# Controllerv2_s_7.net
KiCad netlist of a schematic drawn in EAGLE
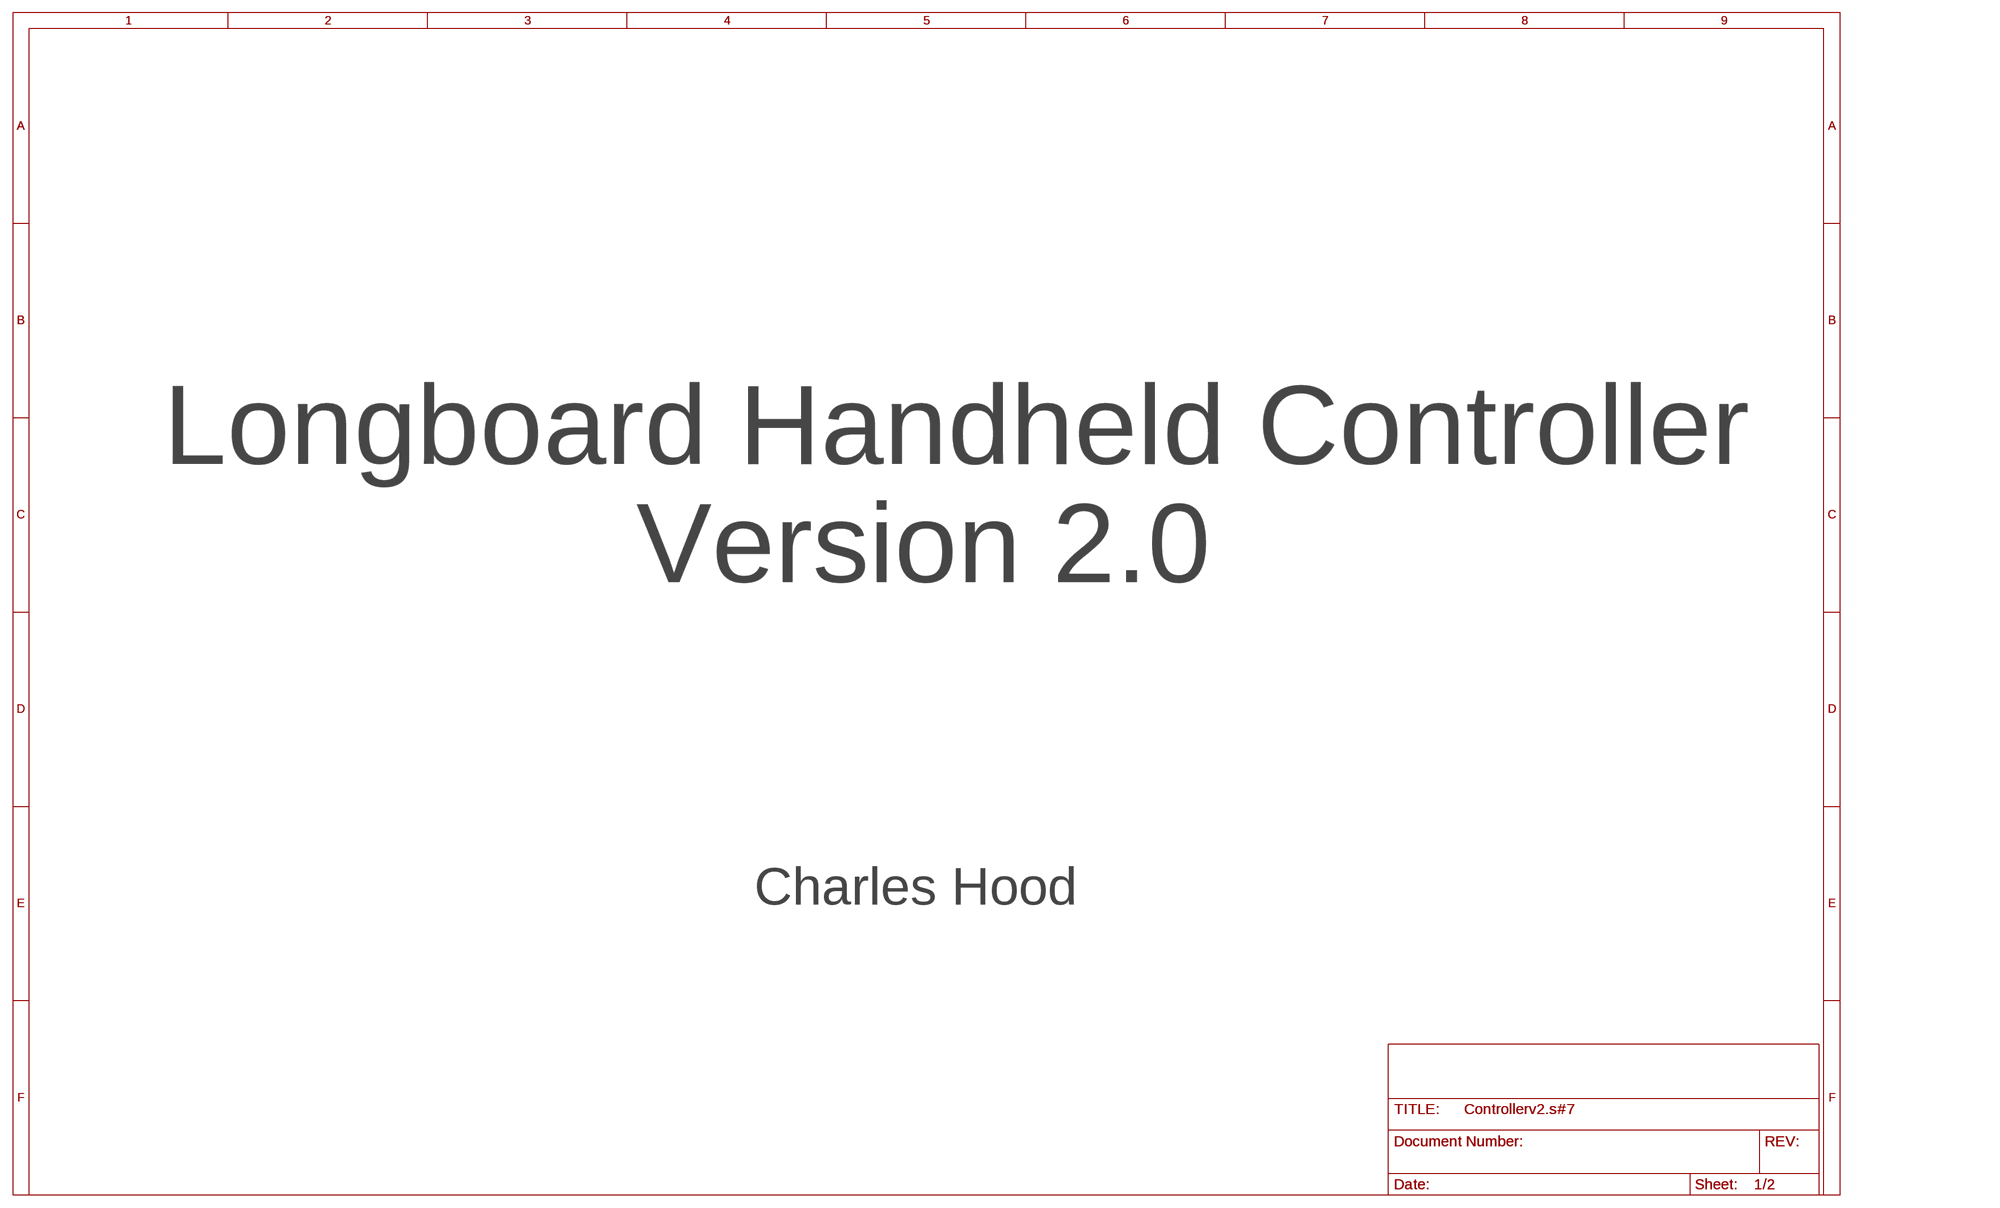
[diagram p0: schematic, sheet 1]
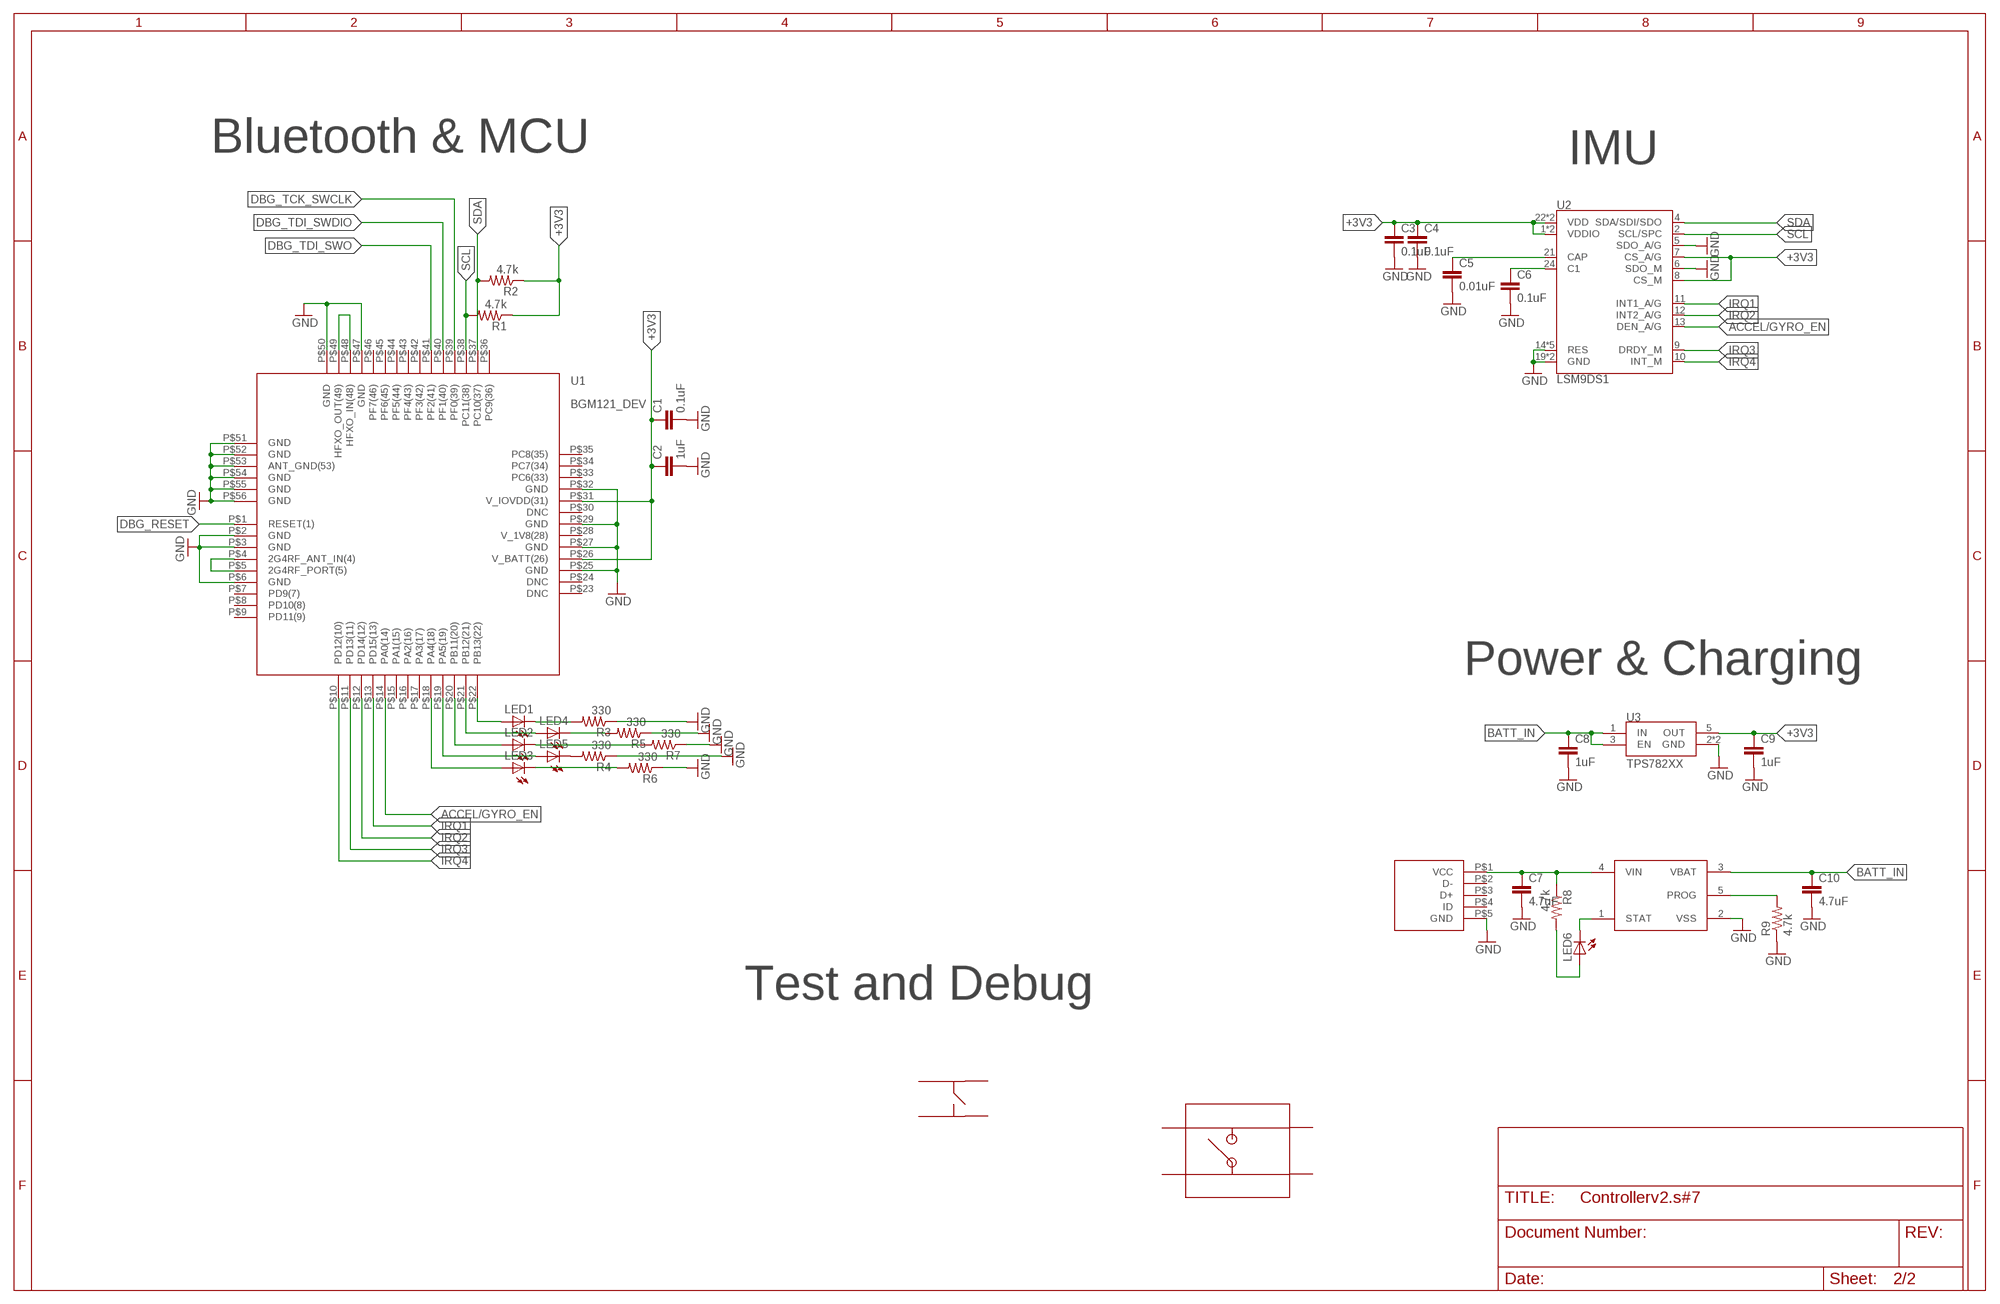
[diagram p1: schematic, sheet 2]

(export (version "E")
  (design (tool "Eeschema 10.0.6"))
  (components
    (comp (ref "C1")
      (value "0.1uF")
      (footprint "eagle-import:C0201")
      (libsource (lib "eagle-import") (part "C-EUC0201"))
    )
    (comp (ref "C2")
      (value "1uF")
      (footprint "eagle-import:C0201")
      (libsource (lib "eagle-import") (part "C-EUC0201"))
    )
    (comp (ref "C3")
      (value "0.1uF")
      (footprint "eagle-import:C0201")
      (libsource (lib "eagle-import") (part "C-EUC0201"))
    )
    (comp (ref "C4")
      (value "0.1uF")
      (footprint "eagle-import:C0201")
      (libsource (lib "eagle-import") (part "C-EUC0201"))
    )
    (comp (ref "C5")
      (value "0.01uF")
      (footprint "eagle-import:C0201")
      (libsource (lib "eagle-import") (part "C-EUC0201"))
    )
    (comp (ref "C6")
      (value "0.1uF")
      (footprint "eagle-import:C0201")
      (libsource (lib "eagle-import") (part "C-EUC0201"))
    )
    (comp (ref "C7")
      (value "4.7uF")
      (footprint "eagle-import:C0402")
      (libsource (lib "eagle-import") (part "C-EUC0402"))
    )
    (comp (ref "C8")
      (value "1uF")
      (footprint "eagle-import:C0201")
      (libsource (lib "eagle-import") (part "C-EUC0201"))
    )
    (comp (ref "C9")
      (value "1uF")
      (footprint "eagle-import:C0201")
      (libsource (lib "eagle-import") (part "C-EUC0201"))
    )
    (comp (ref "C10")
      (value "4.7uF")
      (footprint "eagle-import:C0402")
      (libsource (lib "eagle-import") (part "C-EUC0402"))
    )
    (comp (ref "J1")
      (value "MICRO_USB")
      (footprint "eagle-import:MOLEX_USB")
      (libsource (lib "eagle-import") (part "MICRO_USB"))
    )
    (comp (ref "LED1")
      (value "LEDCHIP-LED0603")
      (footprint "eagle-import:CHIP-LED0603")
      (libsource (lib "eagle-import") (part "LEDCHIP-LED0603"))
    )
    (comp (ref "LED2")
      (value "LEDCHIP-LED0603")
      (footprint "eagle-import:CHIP-LED0603")
      (libsource (lib "eagle-import") (part "LEDCHIP-LED0603"))
    )
    (comp (ref "LED3")
      (value "LEDCHIP-LED0603")
      (footprint "eagle-import:CHIP-LED0603")
      (libsource (lib "eagle-import") (part "LEDCHIP-LED0603"))
    )
    (comp (ref "LED4")
      (value "LEDCHIP-LED0603")
      (footprint "eagle-import:CHIP-LED0603")
      (libsource (lib "eagle-import") (part "LEDCHIP-LED0603"))
    )
    (comp (ref "LED5")
      (value "LEDCHIP-LED0603")
      (footprint "eagle-import:CHIP-LED0603")
      (libsource (lib "eagle-import") (part "LEDCHIP-LED0603"))
    )
    (comp (ref "LED6")
      (value "LEDCHIP-LED0603")
      (footprint "eagle-import:CHIP-LED0603")
      (libsource (lib "eagle-import") (part "LEDCHIP-LED0603"))
    )
    (comp (ref "R1")
      (value "4.7k")
      (footprint "eagle-import:R0201")
      (libsource (lib "eagle-import") (part "R-US_R0201"))
    )
    (comp (ref "R2")
      (value "4.7k")
      (footprint "eagle-import:R0201")
      (libsource (lib "eagle-import") (part "R-US_R0201"))
    )
    (comp (ref "R3")
      (value "330")
      (footprint "eagle-import:R0201")
      (libsource (lib "eagle-import") (part "R-US_R0201"))
    )
    (comp (ref "R4")
      (value "330")
      (footprint "eagle-import:R0201")
      (libsource (lib "eagle-import") (part "R-US_R0201"))
    )
    (comp (ref "R5")
      (value "330")
      (footprint "eagle-import:R0201")
      (libsource (lib "eagle-import") (part "R-US_R0201"))
    )
    (comp (ref "R6")
      (value "330")
      (footprint "eagle-import:R0201")
      (libsource (lib "eagle-import") (part "R-US_R0201"))
    )
    (comp (ref "R7")
      (value "330")
      (footprint "eagle-import:R0201")
      (libsource (lib "eagle-import") (part "R-US_R0201"))
    )
    (comp (ref "R8")
      (value "4.7k")
      (footprint "eagle-import:R0201")
      (libsource (lib "eagle-import") (part "R-US_R0201"))
    )
    (comp (ref "R9")
      (value "4.7k")
      (footprint "eagle-import:R0201")
      (libsource (lib "eagle-import") (part "R-US_R0201"))
    )
    (comp (ref "S1")
      (value "KMR731NG")
      (footprint "eagle-import:KMR731NG")
      (libsource (lib "eagle-import") (part "KMR731NG"))
    )
    (comp (ref "S3")
      (value "PTS840")
      (footprint "eagle-import:PTS840")
      (libsource (lib "eagle-import") (part "PTS840"))
    )
    (comp (ref "U1")
      (value "BGM121_DEV")
      (footprint "eagle-import:BGM121_PAC")
      (libsource (lib "eagle-import") (part "BGM121_DEV"))
    )
    (comp (ref "U2")
      (value "LSM9DS1")
      (footprint "eagle-import:LGA24-8X4")
      (libsource (lib "eagle-import") (part "LSM9DS1"))
    )
    (comp (ref "U3")
      (value "TPS782XX")
      (footprint "eagle-import:SOT23-5L")
      (libsource (lib "eagle-import") (part "TPS782XX"))
    )
    (comp (ref "U4")
      (value "MCP73831")
      (footprint "eagle-import:SOT23-5L")
      (libsource (lib "eagle-import") (part "MCP73831"))
    )
  )
  (nets
    (net (code "1") (name "+3V3") (class "Default")
      (node (ref "C1") (pin "1") (pinfunction "1_1") (pintype "passive"))
      (node (ref "C2") (pin "1") (pinfunction "1_1") (pintype "passive"))
      (node (ref "C3") (pin "1") (pinfunction "1_1") (pintype "passive"))
      (node (ref "C4") (pin "1") (pinfunction "1_1") (pintype "passive"))
      (node (ref "C9") (pin "1") (pinfunction "1_1") (pintype "passive"))
      (node (ref "R1") (pin "1") (pinfunction "1_1") (pintype "passive"))
      (node (ref "R2") (pin "1") (pinfunction "1_1") (pintype "passive"))
      (node (ref "U1") (pin "P$26") (pinfunction "V_BATT(26)_P$26") (pintype "power_in"))
      (node (ref "U1") (pin "P$31") (pinfunction "V_IOVDD(31)_P$31") (pintype "power_in"))
      (node (ref "U2") (pin "1") (pinfunction "VDDIO_1") (pintype "bidirectional"))
      (node (ref "U2") (pin "22") (pinfunction "VDD_22") (pintype "bidirectional"))
      (node (ref "U2") (pin "23") (pinfunction "VDD_23") (pintype "bidirectional"))
      (node (ref "U2") (pin "3") (pinfunction "VDDIO_3") (pintype "bidirectional"))
      (node (ref "U2") (pin "7") (pinfunction "CS_A/G_7") (pintype "bidirectional"))
      (node (ref "U2") (pin "8") (pinfunction "CS_M_8") (pintype "bidirectional"))
      (node (ref "U3") (pin "5") (pinfunction "OUT_5") (pintype "bidirectional"))
    )
    (net (code "2") (name "ACCEL{slash}GYRO_EN") (class "Default")
      (node (ref "U1") (pin "P$14") (pinfunction "PA0(14)_P$14") (pintype "bidirectional"))
      (node (ref "U2") (pin "13") (pinfunction "DEN_A/G_13") (pintype "bidirectional"))
    )
    (net (code "3") (name "BATT_IN") (class "Default")
      (node (ref "C10") (pin "1") (pinfunction "1_1") (pintype "passive"))
      (node (ref "C8") (pin "1") (pinfunction "1_1") (pintype "passive"))
      (node (ref "U3") (pin "1") (pinfunction "IN_1") (pintype "bidirectional"))
      (node (ref "U3") (pin "3") (pinfunction "EN_3") (pintype "bidirectional"))
      (node (ref "U4") (pin "3") (pinfunction "VBAT_3") (pintype "bidirectional"))
    )
    (net (code "4") (name "DBG_RESET") (class "Default")
      (node (ref "U1") (pin "P$1") (pinfunction "RESET(1)_P$1") (pintype "input"))
    )
    (net (code "5") (name "DBG_TCK_SWCLK") (class "Default")
      (node (ref "U1") (pin "P$39") (pinfunction "PF0(39)_P$39") (pintype "bidirectional"))
    )
    (net (code "6") (name "DBG_TDI_SWDIO") (class "Default")
      (node (ref "U1") (pin "P$40") (pinfunction "PF1(40)_P$40") (pintype "bidirectional"))
    )
    (net (code "7") (name "DBG_TDI_SWO") (class "Default")
      (node (ref "U1") (pin "P$41") (pinfunction "PF2(41)_P$41") (pintype "bidirectional"))
    )
    (net (code "8") (name "GND") (class "Default")
      (node (ref "C1") (pin "2") (pinfunction "2_2") (pintype "passive"))
      (node (ref "C10") (pin "2") (pinfunction "2_2") (pintype "passive"))
      (node (ref "C2") (pin "2") (pinfunction "2_2") (pintype "passive"))
      (node (ref "C3") (pin "2") (pinfunction "2_2") (pintype "passive"))
      (node (ref "C4") (pin "2") (pinfunction "2_2") (pintype "passive"))
      (node (ref "C5") (pin "2") (pinfunction "2_2") (pintype "passive"))
      (node (ref "C6") (pin "2") (pinfunction "2_2") (pintype "passive"))
      (node (ref "C7") (pin "2") (pinfunction "2_2") (pintype "passive"))
      (node (ref "C8") (pin "2") (pinfunction "2_2") (pintype "passive"))
      (node (ref "C9") (pin "2") (pinfunction "2_2") (pintype "passive"))
      (node (ref "J1") (pin "P$5") (pinfunction "GND_P$5") (pintype "bidirectional"))
      (node (ref "R3") (pin "1") (pinfunction "1_1") (pintype "passive"))
      (node (ref "R4") (pin "1") (pinfunction "1_1") (pintype "passive"))
      (node (ref "R5") (pin "1") (pinfunction "1_1") (pintype "passive"))
      (node (ref "R6") (pin "1") (pinfunction "1_1") (pintype "passive"))
      (node (ref "R7") (pin "1") (pinfunction "1_1") (pintype "passive"))
      (node (ref "R9") (pin "1") (pinfunction "1_1") (pintype "passive"))
      (node (ref "U1") (pin "P$2") (pinfunction "GND_P$2") (pintype "power_in"))
      (node (ref "U1") (pin "P$25") (pinfunction "GND_P$25") (pintype "power_in"))
      (node (ref "U1") (pin "P$27") (pinfunction "GND_P$27") (pintype "power_in"))
      (node (ref "U1") (pin "P$29") (pinfunction "GND_P$29") (pintype "power_in"))
      (node (ref "U1") (pin "P$3") (pinfunction "GND_P$3") (pintype "power_in"))
      (node (ref "U1") (pin "P$32") (pinfunction "GND_P$32") (pintype "power_in"))
      (node (ref "U1") (pin "P$47") (pinfunction "GND_P$47") (pintype "power_in"))
      (node (ref "U1") (pin "P$50") (pinfunction "GND_P$50") (pintype "power_in"))
      (node (ref "U1") (pin "P$51") (pinfunction "GND_P$51") (pintype "power_in"))
      (node (ref "U1") (pin "P$52") (pinfunction "GND_P$52") (pintype "power_in"))
      (node (ref "U1") (pin "P$53") (pinfunction "ANT_GND(53)_P$53") (pintype "power_in"))
      (node (ref "U1") (pin "P$54") (pinfunction "GND_P$54") (pintype "power_in"))
      (node (ref "U1") (pin "P$55") (pinfunction "GND_P$55") (pintype "power_in"))
      (node (ref "U1") (pin "P$56") (pinfunction "GND_P$56") (pintype "power_in"))
      (node (ref "U1") (pin "P$6") (pinfunction "GND_P$6") (pintype "power_in"))
      (node (ref "U2") (pin "14") (pinfunction "RES_14") (pintype "bidirectional"))
      (node (ref "U2") (pin "15") (pinfunction "RES_15") (pintype "bidirectional"))
      (node (ref "U2") (pin "16") (pinfunction "RES_16") (pintype "bidirectional"))
      (node (ref "U2") (pin "17") (pinfunction "RES_17") (pintype "bidirectional"))
      (node (ref "U2") (pin "18") (pinfunction "RES_18") (pintype "bidirectional"))
      (node (ref "U2") (pin "19") (pinfunction "GND_19") (pintype "bidirectional"))
      (node (ref "U2") (pin "20") (pinfunction "GND_20") (pintype "bidirectional"))
      (node (ref "U2") (pin "5") (pinfunction "SDO_A/G_5") (pintype "bidirectional"))
      (node (ref "U2") (pin "6") (pinfunction "SDO_M_6") (pintype "bidirectional"))
      (node (ref "U3") (pin "2") (pinfunction "GND_2") (pintype "bidirectional"))
      (node (ref "U3") (pin "4") (pinfunction "GND_4") (pintype "bidirectional"))
      (node (ref "U4") (pin "2") (pinfunction "VSS_2") (pintype "bidirectional"))
    )
    (net (code "9") (name "IRQ1") (class "Default")
      (node (ref "U1") (pin "P$13") (pinfunction "PD15(13)_P$13") (pintype "bidirectional"))
      (node (ref "U2") (pin "11") (pinfunction "INT1_A/G_11") (pintype "bidirectional"))
    )
    (net (code "10") (name "IRQ2") (class "Default")
      (node (ref "U1") (pin "P$12") (pinfunction "PD14(12)_P$12") (pintype "bidirectional"))
      (node (ref "U2") (pin "12") (pinfunction "INT2_A/G_12") (pintype "bidirectional"))
    )
    (net (code "11") (name "IRQ3") (class "Default")
      (node (ref "U1") (pin "P$11") (pinfunction "PD13(11)_P$11") (pintype "bidirectional"))
      (node (ref "U2") (pin "9") (pinfunction "DRDY_M_9") (pintype "bidirectional"))
    )
    (net (code "12") (name "IRQ4") (class "Default")
      (node (ref "U1") (pin "P$10") (pinfunction "PD12(10)_P$10") (pintype "bidirectional"))
      (node (ref "U2") (pin "10") (pinfunction "INT_M_10") (pintype "bidirectional"))
    )
    (net (code "13") (name "Net-(J1-VCC)") (class "Default")
      (node (ref "C7") (pin "1") (pinfunction "1_1") (pintype "passive"))
      (node (ref "J1") (pin "P$1") (pinfunction "VCC_P$1") (pintype "bidirectional"))
      (node (ref "R8") (pin "1") (pinfunction "1_1") (pintype "passive"))
      (node (ref "U4") (pin "4") (pinfunction "VIN_4") (pintype "bidirectional"))
    )
    (net (code "14") (name "Net-(LED1-PadC)") (class "Default")
      (node (ref "LED1") (pin "C") (pinfunction "C_C") (pintype "passive"))
      (node (ref "R3") (pin "2") (pinfunction "2_2") (pintype "passive"))
    )
    (net (code "15") (name "Net-(LED2-PadC)") (class "Default")
      (node (ref "LED2") (pin "C") (pinfunction "C_C") (pintype "passive"))
      (node (ref "R7") (pin "2") (pinfunction "2_2") (pintype "passive"))
    )
    (net (code "16") (name "Net-(LED3-PadC)") (class "Default")
      (node (ref "LED3") (pin "C") (pinfunction "C_C") (pintype "passive"))
      (node (ref "R6") (pin "2") (pinfunction "2_2") (pintype "passive"))
    )
    (net (code "17") (name "Net-(LED4-PadC)") (class "Default")
      (node (ref "LED4") (pin "C") (pinfunction "C_C") (pintype "passive"))
      (node (ref "R5") (pin "2") (pinfunction "2_2") (pintype "passive"))
    )
    (net (code "18") (name "Net-(LED5-PadC)") (class "Default")
      (node (ref "LED5") (pin "C") (pinfunction "C_C") (pintype "passive"))
      (node (ref "R4") (pin "2") (pinfunction "2_2") (pintype "passive"))
    )
    (net (code "19") (name "Net-(LED6-PadA)") (class "Default")
      (node (ref "LED6") (pin "A") (pinfunction "A_A") (pintype "passive"))
      (node (ref "R8") (pin "2") (pinfunction "2_2") (pintype "passive"))
    )
    (net (code "20") (name "Net-(U1-2G4RF_ANT_IN(4))") (class "Default")
      (node (ref "U1") (pin "P$4") (pinfunction "2G4RF_ANT_IN(4)_P$4") (pintype "input"))
      (node (ref "U1") (pin "P$5") (pinfunction "2G4RF_PORT(5)_P$5") (pintype "input"))
    )
    (net (code "21") (name "Net-(U1-HFXO_IN(48))") (class "Default")
      (node (ref "U1") (pin "P$48") (pinfunction "HFXO_IN(48)_P$48") (pintype "input"))
      (node (ref "U1") (pin "P$49") (pinfunction "HFXO_OUT(49)_P$49") (pintype "output"))
    )
    (net (code "22") (name "Net-(U1-PA4(18))") (class "Default")
      (node (ref "LED3") (pin "A") (pinfunction "A_A") (pintype "passive"))
      (node (ref "U1") (pin "P$18") (pinfunction "PA4(18)_P$18") (pintype "bidirectional"))
    )
    (net (code "23") (name "Net-(U1-PA5(19))") (class "Default")
      (node (ref "LED5") (pin "A") (pinfunction "A_A") (pintype "passive"))
      (node (ref "U1") (pin "P$19") (pinfunction "PA5(19)_P$19") (pintype "bidirectional"))
    )
    (net (code "24") (name "Net-(U1-PB11(20))") (class "Default")
      (node (ref "LED2") (pin "A") (pinfunction "A_A") (pintype "passive"))
      (node (ref "U1") (pin "P$20") (pinfunction "PB11(20)_P$20") (pintype "bidirectional"))
    )
    (net (code "25") (name "Net-(U1-PB12(21))") (class "Default")
      (node (ref "LED4") (pin "A") (pinfunction "A_A") (pintype "passive"))
      (node (ref "U1") (pin "P$21") (pinfunction "PB12(21)_P$21") (pintype "bidirectional"))
    )
    (net (code "26") (name "Net-(U1-PB13(22))") (class "Default")
      (node (ref "LED1") (pin "A") (pinfunction "A_A") (pintype "passive"))
      (node (ref "U1") (pin "P$22") (pinfunction "PB13(22)_P$22") (pintype "bidirectional"))
    )
    (net (code "27") (name "Net-(U2-C1)") (class "Default")
      (node (ref "C6") (pin "1") (pinfunction "1_1") (pintype "passive"))
      (node (ref "U2") (pin "24") (pinfunction "C1_24") (pintype "bidirectional"))
    )
    (net (code "28") (name "Net-(U2-CAP)") (class "Default")
      (node (ref "C5") (pin "1") (pinfunction "1_1") (pintype "passive"))
      (node (ref "U2") (pin "21") (pinfunction "CAP_21") (pintype "bidirectional"))
    )
    (net (code "29") (name "Net-(U4-PROG)") (class "Default")
      (node (ref "R9") (pin "2") (pinfunction "2_2") (pintype "passive"))
      (node (ref "U4") (pin "5") (pinfunction "PROG_5") (pintype "bidirectional"))
    )
    (net (code "30") (name "Net-(U4-STAT)") (class "Default")
      (node (ref "LED6") (pin "C") (pinfunction "C_C") (pintype "passive"))
      (node (ref "U4") (pin "1") (pinfunction "STAT_1") (pintype "bidirectional"))
    )
    (net (code "31") (name "SCL") (class "Default")
      (node (ref "R1") (pin "2") (pinfunction "2_2") (pintype "passive"))
      (node (ref "U1") (pin "P$38") (pinfunction "PC11(38)_P$38") (pintype "bidirectional"))
      (node (ref "U2") (pin "2") (pinfunction "SCL/SPC_2") (pintype "bidirectional"))
    )
    (net (code "32") (name "SDA") (class "Default")
      (node (ref "R2") (pin "2") (pinfunction "2_2") (pintype "passive"))
      (node (ref "U1") (pin "P$37") (pinfunction "PC10(37)_P$37") (pintype "bidirectional"))
      (node (ref "U2") (pin "4") (pinfunction "SDA/SDI/SDO_4") (pintype "bidirectional"))
    )
    (net (code "33") (name "V_1V8(28)") (class "Default")
      (node (ref "U1") (pin "P$28") (pinfunction "V_1V8(28)_P$28") (pintype "power_in"))
    )
    (net (code "34") (name "unconnected-(J1-D+-PadP$3)") (class "Default")
      (node (ref "J1") (pin "P$3") (pinfunction "D+_P$3") (pintype "bidirectional"))
    )
    (net (code "35") (name "unconnected-(J1-D--PadP$2)") (class "Default")
      (node (ref "J1") (pin "P$2") (pinfunction "D-_P$2") (pintype "bidirectional"))
    )
    (net (code "36") (name "unconnected-(J1-ID-PadP$4)") (class "Default")
      (node (ref "J1") (pin "P$4") (pinfunction "ID_P$4") (pintype "bidirectional"))
    )
    (net (code "37") (name "unconnected-(S1-PadP$1)") (class "Default")
      (node (ref "S1") (pin "P$1") (pinfunction "P$1_P$1") (pintype "bidirectional"))
    )
    (net (code "38") (name "unconnected-(S1-PadP$2)") (class "Default")
      (node (ref "S1") (pin "P$2") (pinfunction "P$2_P$2") (pintype "bidirectional"))
    )
    (net (code "39") (name "unconnected-(S1-PadP$3)") (class "Default")
      (node (ref "S1") (pin "P$3") (pinfunction "P$3_P$3") (pintype "bidirectional"))
    )
    (net (code "40") (name "unconnected-(S1-PadP$4)") (class "Default")
      (node (ref "S1") (pin "P$4") (pinfunction "P$4_P$4") (pintype "bidirectional"))
    )
    (net (code "41") (name "unconnected-(S3-Pad1)") (class "Default")
      (node (ref "S3") (pin "1") (pinfunction "1_1") (pintype "bidirectional"))
    )
    (net (code "42") (name "unconnected-(S3-Pad2)") (class "Default")
      (node (ref "S3") (pin "2") (pinfunction "2_2") (pintype "bidirectional"))
    )
    (net (code "43") (name "unconnected-(S3-Pad3)") (class "Default")
      (node (ref "S3") (pin "3") (pinfunction "3_3") (pintype "bidirectional"))
    )
    (net (code "44") (name "unconnected-(S3-Pad4)") (class "Default")
      (node (ref "S3") (pin "4") (pinfunction "4_4") (pintype "bidirectional"))
    )
    (net (code "45") (name "unconnected-(U1-DNC-PadP$23)") (class "Default")
      (node (ref "U1") (pin "P$23") (pinfunction "DNC_P$23") (pintype "no_connect"))
    )
    (net (code "46") (name "unconnected-(U1-DNC-PadP$24)") (class "Default")
      (node (ref "U1") (pin "P$24") (pinfunction "DNC_P$24") (pintype "no_connect"))
    )
    (net (code "47") (name "unconnected-(U1-DNC-PadP$30)") (class "Default")
      (node (ref "U1") (pin "P$30") (pinfunction "DNC_P$30") (pintype "no_connect"))
    )
    (net (code "48") (name "unconnected-(U1-PA1(15)-PadP$15)") (class "Default")
      (node (ref "U1") (pin "P$15") (pinfunction "PA1(15)_P$15") (pintype "bidirectional"))
    )
    (net (code "49") (name "unconnected-(U1-PA2(16)-PadP$16)") (class "Default")
      (node (ref "U1") (pin "P$16") (pinfunction "PA2(16)_P$16") (pintype "bidirectional"))
    )
    (net (code "50") (name "unconnected-(U1-PA3(17)-PadP$17)") (class "Default")
      (node (ref "U1") (pin "P$17") (pinfunction "PA3(17)_P$17") (pintype "bidirectional"))
    )
    (net (code "51") (name "unconnected-(U1-PC6(33)-PadP$33)") (class "Default")
      (node (ref "U1") (pin "P$33") (pinfunction "PC6(33)_P$33") (pintype "bidirectional"))
    )
    (net (code "52") (name "unconnected-(U1-PC7(34)-PadP$34)") (class "Default")
      (node (ref "U1") (pin "P$34") (pinfunction "PC7(34)_P$34") (pintype "bidirectional"))
    )
    (net (code "53") (name "unconnected-(U1-PC8(35)-PadP$35)") (class "Default")
      (node (ref "U1") (pin "P$35") (pinfunction "PC8(35)_P$35") (pintype "bidirectional"))
    )
    (net (code "54") (name "unconnected-(U1-PC9(36)-PadP$36)") (class "Default")
      (node (ref "U1") (pin "P$36") (pinfunction "PC9(36)_P$36") (pintype "bidirectional"))
    )
    (net (code "55") (name "unconnected-(U1-PD9(7)-PadP$7)") (class "Default")
      (node (ref "U1") (pin "P$7") (pinfunction "PD9(7)_P$7") (pintype "bidirectional"))
    )
    (net (code "56") (name "unconnected-(U1-PD10(8)-PadP$8)") (class "Default")
      (node (ref "U1") (pin "P$8") (pinfunction "PD10(8)_P$8") (pintype "bidirectional"))
    )
    (net (code "57") (name "unconnected-(U1-PD11(9)-PadP$9)") (class "Default")
      (node (ref "U1") (pin "P$9") (pinfunction "PD11(9)_P$9") (pintype "bidirectional"))
    )
    (net (code "58") (name "unconnected-(U1-PF3(42)-PadP$42)") (class "Default")
      (node (ref "U1") (pin "P$42") (pinfunction "PF3(42)_P$42") (pintype "bidirectional"))
    )
    (net (code "59") (name "unconnected-(U1-PF4(43)-PadP$43)") (class "Default")
      (node (ref "U1") (pin "P$43") (pinfunction "PF4(43)_P$43") (pintype "bidirectional"))
    )
    (net (code "60") (name "unconnected-(U1-PF5(44)-PadP$44)") (class "Default")
      (node (ref "U1") (pin "P$44") (pinfunction "PF5(44)_P$44") (pintype "bidirectional"))
    )
    (net (code "61") (name "unconnected-(U1-PF6(45)-PadP$45)") (class "Default")
      (node (ref "U1") (pin "P$45") (pinfunction "PF6(45)_P$45") (pintype "bidirectional"))
    )
    (net (code "62") (name "unconnected-(U1-PF7(46)-PadP$46)") (class "Default")
      (node (ref "U1") (pin "P$46") (pinfunction "PF7(46)_P$46") (pintype "bidirectional"))
    )
  )
)
